# Modes.net
KiCad netlist of a schematic drawn in Altium Designer
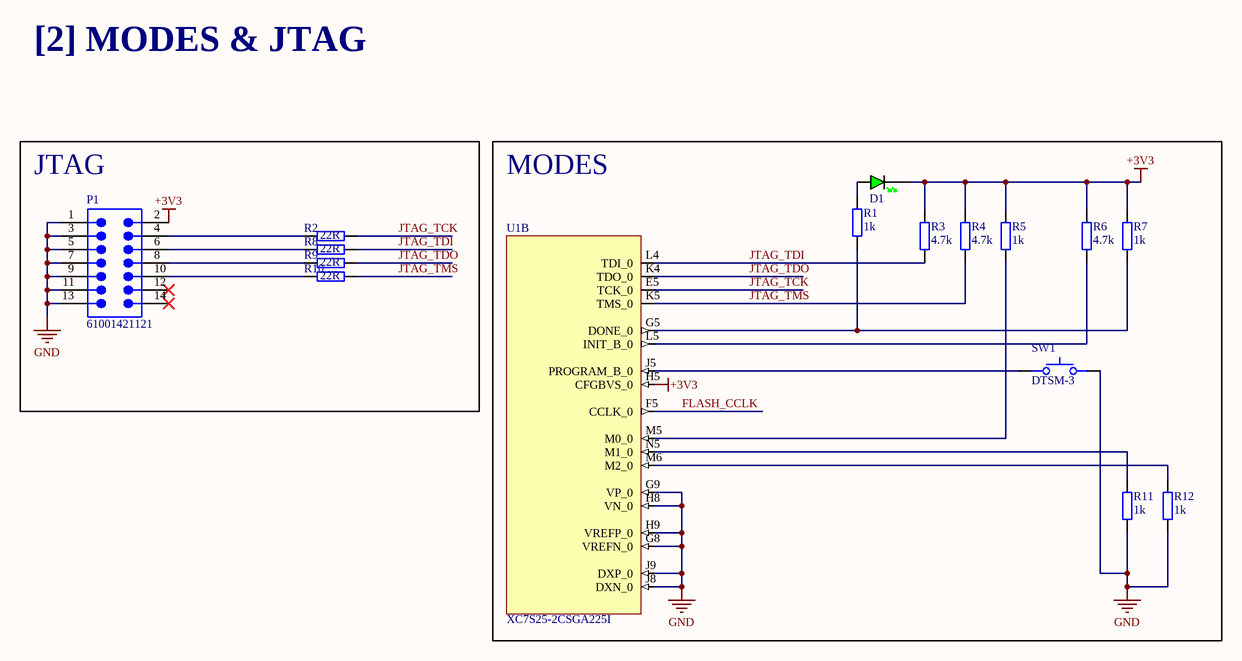
[diagram p0: Modes.SchDoc]

(export (version "E")
  (design (tool "Eeschema 10.0.6"))
  (components
    (comp (ref "D1")
      (value "GREEN")
      (footprint "LED_0402_GREEN")
      (description "LED 0402 GREEN SMD")
      (libsource (lib "Schematic-Lib-PhilsLab") (part "LED_0402_GREEN"))
    )
    (comp (ref "P1")
      (value "61001421121")
      (footprint "61001421121")
      (libsource (lib "Altium Content Vault") (part "Header_Male_2R_14P"))
    )
    (comp (ref "R1")
      (value "1k")
      (footprint "RES_0402")
      (description "Resistor SMD 0402")
      (libsource (lib "Schematic-Lib-PhilsLab") (part "RES_0402"))
    )
    (comp (ref "R2")
      (value "22R")
      (footprint "RES_0402")
      (description "Resistor SMD 0402")
      (libsource (lib "Schematic-Lib-PhilsLab") (part "RES_0402"))
    )
    (comp (ref "R3")
      (value "4.7k")
      (footprint "RES_0402")
      (description "Resistor SMD 0402")
      (libsource (lib "Schematic-Lib-PhilsLab") (part "RES_0402"))
    )
    (comp (ref "R4")
      (value "4.7k")
      (footprint "RES_0402")
      (description "Resistor SMD 0402")
      (libsource (lib "Schematic-Lib-PhilsLab") (part "RES_0402"))
    )
    (comp (ref "R5")
      (value "1k")
      (footprint "RES_0201")
      (description "Resistor SMD 0201")
      (libsource (lib "Schematic-Lib-PhilsLab") (part "RES_0201"))
    )
    (comp (ref "R6")
      (value "4.7k")
      (footprint "RES_0402")
      (description "Resistor SMD 0402")
      (libsource (lib "Schematic-Lib-PhilsLab") (part "RES_0402"))
    )
    (comp (ref "R7")
      (value "1k")
      (footprint "RES_0402")
      (description "Resistor SMD 0402")
      (libsource (lib "Schematic-Lib-PhilsLab") (part "RES_0402"))
    )
    (comp (ref "R8")
      (value "22R")
      (footprint "RES_0402")
      (description "Resistor SMD 0402")
      (libsource (lib "Schematic-Lib-PhilsLab") (part "RES_0402"))
    )
    (comp (ref "R9")
      (value "22R")
      (footprint "RES_0402")
      (description "Resistor SMD 0402")
      (libsource (lib "Schematic-Lib-PhilsLab") (part "RES_0402"))
    )
    (comp (ref "R10")
      (value "22R")
      (footprint "RES_0402")
      (description "Resistor SMD 0402")
      (libsource (lib "Schematic-Lib-PhilsLab") (part "RES_0402"))
    )
    (comp (ref "R11")
      (value "1k")
      (footprint "RES_0201")
      (description "Resistor SMD 0201")
      (libsource (lib "Schematic-Lib-PhilsLab") (part "RES_0201"))
    )
    (comp (ref "R12")
      (value "1k")
      (footprint "RES_0201")
      (description "Resistor SMD 0201")
      (libsource (lib "Schematic-Lib-PhilsLab") (part "RES_0201"))
    )
    (comp (ref "SW1")
      (value "DTSM-3")
      (footprint "DTSM-3")
      (description "Tactile Switch SMD SPST")
      (fields (field (name "MANUFACTURER") "Diptronics"))
      (libsource (lib "Schematic-Lib-PhilsLab") (part "DTSM-3"))
    )
    (comp (ref "U1")
      (value "XC7S25-2CSGA225I")
      (footprint "CSGA225")
      (fields (field (name "MANUFACTURER") "Xilinx"))
      (libsource (lib "Schematic-Lib-PhilsLab") (part "XC7S25-2CSGA225I"))
    )
  )
  (nets
    (net (code "1") (name "+3V3") (class "Default")
      (node (ref "D1") (pin "K") (pinfunction "K_K") (pintype "passive"))
      (node (ref "P1") (pin "2") (pinfunction "2_2") (pintype "passive"))
      (node (ref "R3") (pin "2") (pinfunction "2_2") (pintype "passive"))
      (node (ref "R4") (pin "2") (pinfunction "2_2") (pintype "passive"))
      (node (ref "R5") (pin "2") (pinfunction "2_2") (pintype "passive"))
      (node (ref "R6") (pin "2") (pinfunction "2_2") (pintype "passive"))
      (node (ref "R7") (pin "2") (pinfunction "2_2") (pintype "passive"))
      (node (ref "U1") (pin "H5") (pinfunction "CFGBVS_0_H5") (pintype "input"))
    )
    (net (code "2") (name "/FLASH_CCLK") (class "Default")
      (node (ref "U1") (pin "F5") (pinfunction "CCLK_0_F5") (pintype "output"))
    )
    (net (code "3") (name "/JTAG_TCK") (class "Default")
      (node (ref "R2") (pin "2") (pinfunction "2_2") (pintype "passive"))
      (node (ref "U1") (pin "E5") (pinfunction "TCK_0_E5") (pintype "bidirectional"))
    )
    (net (code "4") (name "/JTAG_TDI") (class "Default")
      (node (ref "R3") (pin "1") (pinfunction "1_1") (pintype "passive"))
      (node (ref "R8") (pin "2") (pinfunction "2_2") (pintype "passive"))
      (node (ref "U1") (pin "L4") (pinfunction "TDI_0_L4") (pintype "bidirectional"))
    )
    (net (code "5") (name "/JTAG_TDO") (class "Default")
      (node (ref "R9") (pin "2") (pinfunction "2_2") (pintype "passive"))
      (node (ref "U1") (pin "K4") (pinfunction "TDO_0_K4") (pintype "bidirectional"))
    )
    (net (code "6") (name "/JTAG_TMS") (class "Default")
      (node (ref "R10") (pin "2") (pinfunction "2_2") (pintype "passive"))
      (node (ref "R4") (pin "1") (pinfunction "1_1") (pintype "passive"))
      (node (ref "U1") (pin "K5") (pinfunction "TMS_0_K5") (pintype "bidirectional"))
    )
    (net (code "7") (name "GND") (class "Default")
      (node (ref "P1") (pin "1") (pinfunction "1_1") (pintype "passive"))
      (node (ref "P1") (pin "11") (pinfunction "11_11") (pintype "passive"))
      (node (ref "P1") (pin "13") (pinfunction "13_13") (pintype "passive"))
      (node (ref "P1") (pin "3") (pinfunction "3_3") (pintype "passive"))
      (node (ref "P1") (pin "5") (pinfunction "5_5") (pintype "passive"))
      (node (ref "P1") (pin "7") (pinfunction "7_7") (pintype "passive"))
      (node (ref "P1") (pin "9") (pinfunction "9_9") (pintype "passive"))
      (node (ref "R11") (pin "1") (pinfunction "1_1") (pintype "passive"))
      (node (ref "R12") (pin "1") (pinfunction "1_1") (pintype "passive"))
      (node (ref "SW1") (pin "1") (pintype "passive"))
      (node (ref "U1") (pin "G8") (pinfunction "VREFN_0_G8") (pintype "input"))
      (node (ref "U1") (pin "G9") (pinfunction "VP_0_G9") (pintype "input"))
      (node (ref "U1") (pin "H8") (pinfunction "VN_0_H8") (pintype "input"))
      (node (ref "U1") (pin "H9") (pinfunction "VREFP_0_H9") (pintype "input"))
      (node (ref "U1") (pin "J8") (pinfunction "DXN_0_J8") (pintype "input"))
      (node (ref "U1") (pin "J9") (pinfunction "DXP_0_J9") (pintype "input"))
    )
    (net (code "8") (name "Net-(D1-PadA)") (class "Default")
      (node (ref "D1") (pin "A") (pinfunction "A_A") (pintype "passive"))
      (node (ref "R1") (pin "1") (pinfunction "1_1") (pintype "passive"))
    )
    (net (code "9") (name "Net-(P1-Pad4)") (class "Default")
      (node (ref "P1") (pin "4") (pinfunction "4_4") (pintype "passive"))
      (node (ref "R2") (pin "1") (pinfunction "1_1") (pintype "passive"))
    )
    (net (code "10") (name "Net-(P1-Pad6)") (class "Default")
      (node (ref "P1") (pin "6") (pinfunction "6_6") (pintype "passive"))
      (node (ref "R8") (pin "1") (pinfunction "1_1") (pintype "passive"))
    )
    (net (code "11") (name "Net-(P1-Pad8)") (class "Default")
      (node (ref "P1") (pin "8") (pinfunction "8_8") (pintype "passive"))
      (node (ref "R9") (pin "1") (pinfunction "1_1") (pintype "passive"))
    )
    (net (code "12") (name "Net-(P1-Pad10)") (class "Default")
      (node (ref "P1") (pin "10") (pinfunction "10_10") (pintype "passive"))
      (node (ref "R10") (pin "1") (pinfunction "1_1") (pintype "passive"))
    )
    (net (code "13") (name "Net-(U1B-DONE_0)") (class "Default")
      (node (ref "R1") (pin "2") (pinfunction "2_2") (pintype "passive"))
      (node (ref "R7") (pin "1") (pinfunction "1_1") (pintype "passive"))
      (node (ref "U1") (pin "G5") (pinfunction "DONE_0_G5") (pintype "output"))
    )
    (net (code "14") (name "Net-(U1B-INIT_B_0)") (class "Default")
      (node (ref "R6") (pin "1") (pinfunction "1_1") (pintype "passive"))
      (node (ref "U1") (pin "L5") (pinfunction "INIT_B_0_L5") (pintype "output"))
    )
    (net (code "15") (name "Net-(U1B-M0_0)") (class "Default")
      (node (ref "R5") (pin "1") (pinfunction "1_1") (pintype "passive"))
      (node (ref "U1") (pin "M5") (pinfunction "M0_0_M5") (pintype "input"))
    )
    (net (code "16") (name "Net-(U1B-M1_0)") (class "Default")
      (node (ref "R11") (pin "2") (pinfunction "2_2") (pintype "passive"))
      (node (ref "U1") (pin "N5") (pinfunction "M1_0_N5") (pintype "input"))
    )
    (net (code "17") (name "Net-(U1B-M2_0)") (class "Default")
      (node (ref "R12") (pin "2") (pinfunction "2_2") (pintype "passive"))
      (node (ref "U1") (pin "M6") (pinfunction "M2_0_M6") (pintype "input"))
    )
    (net (code "18") (name "Net-(U1B-PROGRAM_B_0)") (class "Default")
      (node (ref "SW1") (pin "2") (pintype "passive"))
      (node (ref "U1") (pin "J5") (pinfunction "PROGRAM_B_0_J5") (pintype "input"))
    )
    (net (code "19") (name "unconnected-(P1-Pad12)") (class "Default")
      (node (ref "P1") (pin "12") (pinfunction "12_12") (pintype "passive+no_connect"))
    )
    (net (code "20") (name "unconnected-(P1-Pad14)") (class "Default")
      (node (ref "P1") (pin "14") (pinfunction "14_14") (pintype "passive+no_connect"))
    )
  )
)
